# Thermal_MGMT.net
KiCad netlist of a schematic drawn in Altium Designer
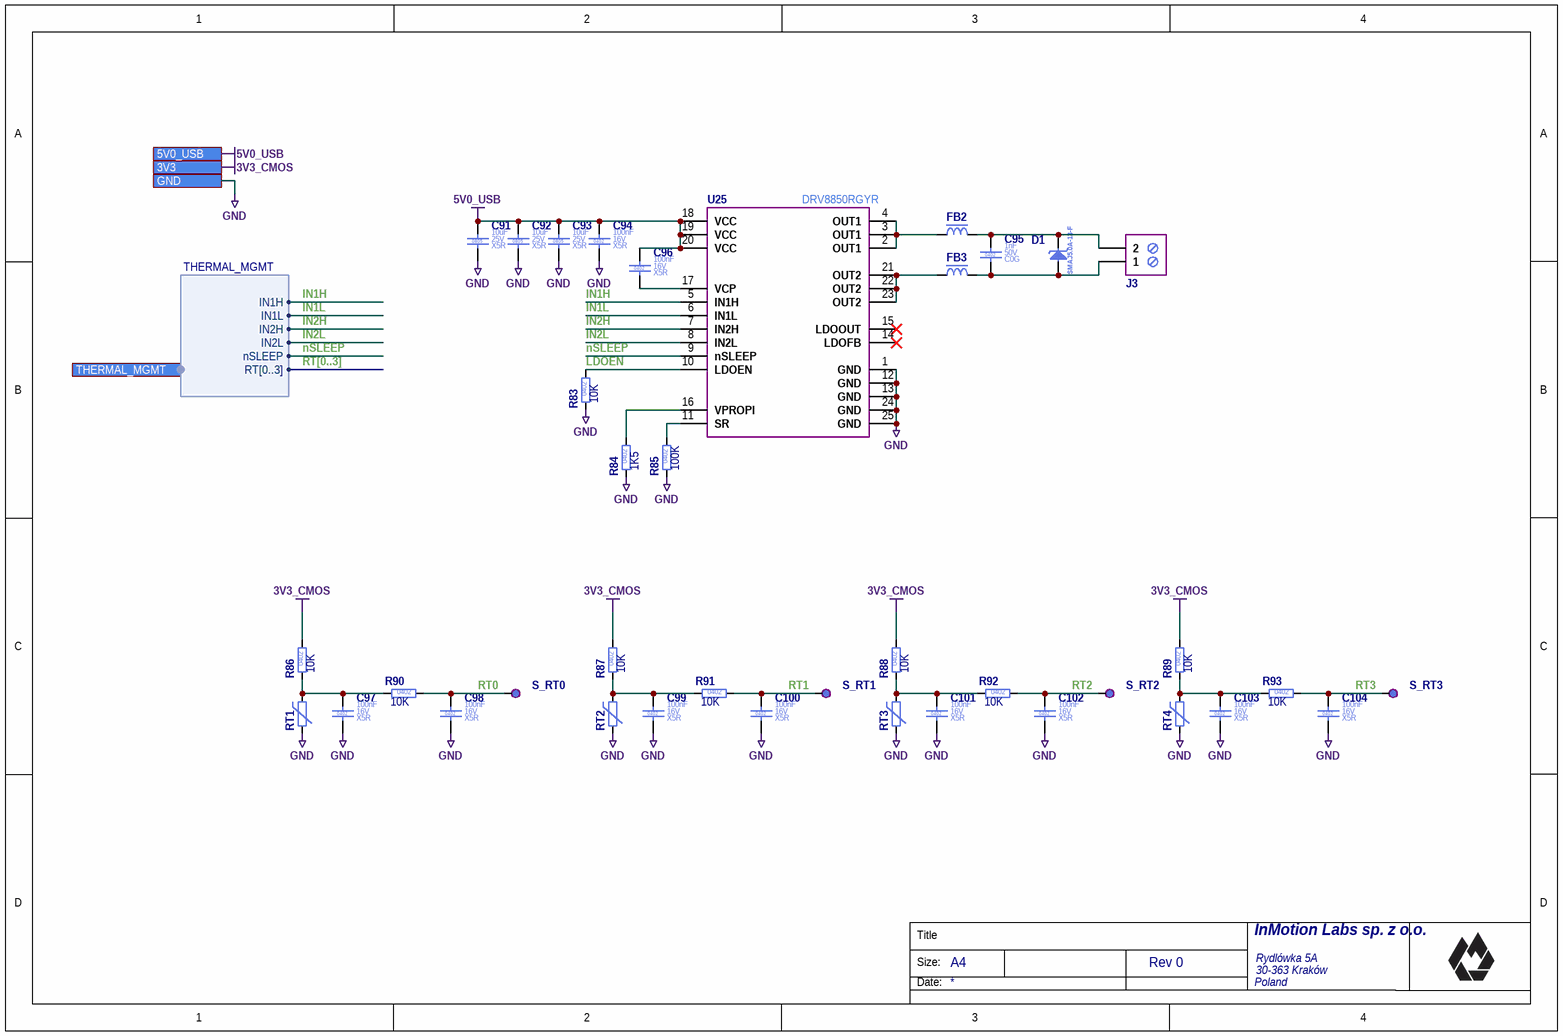
[diagram p0: Thermal_MGMT.SchDoc]

(export (version "E")
  (design (tool "Eeschema 10.0.6"))
  (components
    (comp (ref "C91")
      (value "C_10UF_25V_X5R_0805_10")
      (footprint "C_0805_2012")
      (description "Ceramic Capacitor")
      (fields
        (field (name "CASE/PACKAGE") "0805")
        (field (name "VOLTAGE RATING (DC)") "25V")
        (field (name "DIELECTRIC") "X5R")
        (field (name "CAPACITANCE") "10uF")
        (field (name "TOLERANCE") "10%")
        (field (name "MANUFACTURER PART NUMBER") "CL21A106KAYNNNE")
      )
      (libsource (lib "7Sigma") (part "C"))
    )
    (comp (ref "C92")
      (value "C_10UF_25V_X5R_0805_10")
      (footprint "C_0805_2012")
      (description "Ceramic Capacitor")
      (fields
        (field (name "CASE/PACKAGE") "0805")
        (field (name "VOLTAGE RATING (DC)") "25V")
        (field (name "DIELECTRIC") "X5R")
        (field (name "CAPACITANCE") "10uF")
        (field (name "TOLERANCE") "10%")
        (field (name "MANUFACTURER PART NUMBER") "CL21A106KAYNNNE")
      )
      (libsource (lib "7Sigma") (part "C"))
    )
    (comp (ref "C93")
      (value "C_10UF_25V_X5R_0805_10")
      (footprint "C_0805_2012")
      (description "Ceramic Capacitor")
      (fields
        (field (name "CASE/PACKAGE") "0805")
        (field (name "VOLTAGE RATING (DC)") "25V")
        (field (name "DIELECTRIC") "X5R")
        (field (name "CAPACITANCE") "10uF")
        (field (name "TOLERANCE") "10%")
        (field (name "MANUFACTURER PART NUMBER") "CL21A106KAYNNNE")
      )
      (libsource (lib "7Sigma") (part "C"))
    )
    (comp (ref "C94")
      (value "C_100NF_16V_X5R_0402_10")
      (footprint "C_0402_1005")
      (description "Ceramic Capacitor")
      (fields
        (field (name "CASE/PACKAGE") "0402")
        (field (name "VOLTAGE RATING (DC)") "16V")
        (field (name "DIELECTRIC") "X5R")
        (field (name "CAPACITANCE") "100nF")
        (field (name "TOLERANCE") "10%")
        (field (name "MANUFACTURER PART NUMBER") "EMK105BJ104KV-F")
      )
      (libsource (lib "7Sigma") (part "C"))
    )
    (comp (ref "C95")
      (value "C_1NF_50V_C0G_0402_5")
      (footprint "C_0402_1005")
      (description "Ceramic Capacitor")
      (fields
        (field (name "CASE/PACKAGE") "0402")
        (field (name "VOLTAGE RATING (DC)") "50V")
        (field (name "DIELECTRIC") "C0G")
        (field (name "CAPACITANCE") "1nF")
        (field (name "TOLERANCE") "5%")
        (field (name "MANUFACTURER PART NUMBER") "UMK105CG102JV-F")
      )
      (libsource (lib "7Sigma") (part "C"))
    )
    (comp (ref "C96")
      (value "C_100NF_16V_X5R_0402_10")
      (footprint "C_0402_1005")
      (description "Ceramic Capacitor")
      (fields
        (field (name "CASE/PACKAGE") "0402")
        (field (name "VOLTAGE RATING (DC)") "16V")
        (field (name "DIELECTRIC") "X5R")
        (field (name "CAPACITANCE") "100nF")
        (field (name "TOLERANCE") "10%")
        (field (name "MANUFACTURER PART NUMBER") "EMK105BJ104KV-F")
      )
      (libsource (lib "7Sigma") (part "C"))
    )
    (comp (ref "C97")
      (value "C_100NF_16V_X5R_0402_10")
      (footprint "C_0402_1005")
      (description "Ceramic Capacitor")
      (fields
        (field (name "CASE/PACKAGE") "0402")
        (field (name "VOLTAGE RATING (DC)") "16V")
        (field (name "DIELECTRIC") "X5R")
        (field (name "CAPACITANCE") "100nF")
        (field (name "TOLERANCE") "10%")
        (field (name "MANUFACTURER PART NUMBER") "EMK105BJ104KV-F")
      )
      (libsource (lib "7Sigma") (part "C"))
    )
    (comp (ref "C98")
      (value "C_100NF_16V_X5R_0402_10")
      (footprint "C_0402_1005")
      (description "Ceramic Capacitor")
      (fields
        (field (name "CASE/PACKAGE") "0402")
        (field (name "VOLTAGE RATING (DC)") "16V")
        (field (name "DIELECTRIC") "X5R")
        (field (name "CAPACITANCE") "100nF")
        (field (name "TOLERANCE") "10%")
        (field (name "MANUFACTURER PART NUMBER") "EMK105BJ104KV-F")
      )
      (libsource (lib "7Sigma") (part "C"))
    )
    (comp (ref "C99")
      (value "C_100NF_16V_X5R_0402_10")
      (footprint "C_0402_1005")
      (description "Ceramic Capacitor")
      (fields
        (field (name "CASE/PACKAGE") "0402")
        (field (name "VOLTAGE RATING (DC)") "16V")
        (field (name "DIELECTRIC") "X5R")
        (field (name "CAPACITANCE") "100nF")
        (field (name "TOLERANCE") "10%")
        (field (name "MANUFACTURER PART NUMBER") "EMK105BJ104KV-F")
      )
      (libsource (lib "7Sigma") (part "C"))
    )
    (comp (ref "C100")
      (value "C_100NF_16V_X5R_0402_10")
      (footprint "C_0402_1005")
      (description "Ceramic Capacitor")
      (fields
        (field (name "CASE/PACKAGE") "0402")
        (field (name "VOLTAGE RATING (DC)") "16V")
        (field (name "DIELECTRIC") "X5R")
        (field (name "CAPACITANCE") "100nF")
        (field (name "TOLERANCE") "10%")
        (field (name "MANUFACTURER PART NUMBER") "EMK105BJ104KV-F")
      )
      (libsource (lib "7Sigma") (part "C"))
    )
    (comp (ref "C101")
      (value "C_100NF_16V_X5R_0402_10")
      (footprint "C_0402_1005")
      (description "Ceramic Capacitor")
      (fields
        (field (name "CASE/PACKAGE") "0402")
        (field (name "VOLTAGE RATING (DC)") "16V")
        (field (name "DIELECTRIC") "X5R")
        (field (name "CAPACITANCE") "100nF")
        (field (name "TOLERANCE") "10%")
        (field (name "MANUFACTURER PART NUMBER") "EMK105BJ104KV-F")
      )
      (libsource (lib "7Sigma") (part "C"))
    )
    (comp (ref "C102")
      (value "C_100NF_16V_X5R_0402_10")
      (footprint "C_0402_1005")
      (description "Ceramic Capacitor")
      (fields
        (field (name "CASE/PACKAGE") "0402")
        (field (name "VOLTAGE RATING (DC)") "16V")
        (field (name "DIELECTRIC") "X5R")
        (field (name "CAPACITANCE") "100nF")
        (field (name "TOLERANCE") "10%")
        (field (name "MANUFACTURER PART NUMBER") "EMK105BJ104KV-F")
      )
      (libsource (lib "7Sigma") (part "C"))
    )
    (comp (ref "C103")
      (value "C_100NF_16V_X5R_0402_10")
      (footprint "C_0402_1005")
      (description "Ceramic Capacitor")
      (fields
        (field (name "CASE/PACKAGE") "0402")
        (field (name "VOLTAGE RATING (DC)") "16V")
        (field (name "DIELECTRIC") "X5R")
        (field (name "CAPACITANCE") "100nF")
        (field (name "TOLERANCE") "10%")
        (field (name "MANUFACTURER PART NUMBER") "EMK105BJ104KV-F")
      )
      (libsource (lib "7Sigma") (part "C"))
    )
    (comp (ref "C104")
      (value "C_100NF_16V_X5R_0402_10")
      (footprint "C_0402_1005")
      (description "Ceramic Capacitor")
      (fields
        (field (name "CASE/PACKAGE") "0402")
        (field (name "VOLTAGE RATING (DC)") "16V")
        (field (name "DIELECTRIC") "X5R")
        (field (name "CAPACITANCE") "100nF")
        (field (name "TOLERANCE") "10%")
        (field (name "MANUFACTURER PART NUMBER") "EMK105BJ104KV-F")
      )
      (libsource (lib "7Sigma") (part "C"))
    )
    (comp (ref "D1")
      (value "SMAJ5.0A-13-F")
      (footprint "DO-214AC")
      (description "ESD Suppressors / TVS Diodes")
      (fields (field (name "PART NUMBER") "SMAJ5.0A-13-F") (field (name "MANUFACTURER") "Diodes Inc"))
      (libsource (lib "7Sigma") (part "TVS_UNI"))
    )
    (comp (ref "FB2")
      (value "FBMJ1608HS220NTR")
      (footprint "FB_0603_1608")
      (description "Ferrite Bead")
      (fields (field (name "MANUFACTURER") "Taiyo Yuden") (field (name "TOLERANCE") "30"))
      (libsource (lib "7Sigma") (part "FB"))
    )
    (comp (ref "FB3")
      (value "FBMJ1608HS220NTR")
      (footprint "FB_0603_1608")
      (description "Ferrite Bead")
      (fields (field (name "MANUFACTURER") "Taiyo Yuden") (field (name "TOLERANCE") "30"))
      (libsource (lib "7Sigma") (part "FB"))
    )
    (comp (ref "J3")
      (value "691101710002")
      (footprint "691101710002")
      (description "PCB Terminal Block 1x2")
      (fields (field (name "MANUFACTURER") "Wurth Elektronik"))
      (libsource (lib "7Sigma") (part "ARK2"))
    )
    (comp (ref "R83")
      (value "R_10K_0402_1")
      (footprint "R_0402_1005")
      (description "Thick Film Resistor")
      (fields
        (field (name "RESISTANCE") "10K")
        (field (name "CASE/PACKAGE") "0402")
        (field (name "TOLERANCE") "1%")
        (field (name "MANUFACTURER") "Yageo")
      )
      (libsource (lib "7Sigma") (part "R"))
    )
    (comp (ref "R84")
      (value "R_1K5_0402_1")
      (footprint "R_0402_1005")
      (description "Thick Film Resistor")
      (fields
        (field (name "RESISTANCE") "1K5")
        (field (name "CASE/PACKAGE") "0402")
        (field (name "TOLERANCE") "1%")
        (field (name "MANUFACTURER") "Yageo")
      )
      (libsource (lib "7Sigma") (part "R"))
    )
    (comp (ref "R85")
      (value "R_100K_0402_1")
      (footprint "R_0402_1005")
      (description "Thick Film Resistor")
      (fields
        (field (name "RESISTANCE") "100K")
        (field (name "CASE/PACKAGE") "0402")
        (field (name "TOLERANCE") "1%")
        (field (name "MANUFACTURER") "Yageo")
      )
      (libsource (lib "7Sigma") (part "R"))
    )
    (comp (ref "R86")
      (value "R_10K_0402_1")
      (footprint "R_0402_1005")
      (description "Thick Film Resistor")
      (fields
        (field (name "RESISTANCE") "10K")
        (field (name "CASE/PACKAGE") "0402")
        (field (name "TOLERANCE") "1%")
        (field (name "MANUFACTURER") "Yageo")
      )
      (libsource (lib "7Sigma") (part "R"))
    )
    (comp (ref "R87")
      (value "R_10K_0402_1")
      (footprint "R_0402_1005")
      (description "Thick Film Resistor")
      (fields
        (field (name "RESISTANCE") "10K")
        (field (name "CASE/PACKAGE") "0402")
        (field (name "TOLERANCE") "1%")
        (field (name "MANUFACTURER") "Yageo")
      )
      (libsource (lib "7Sigma") (part "R"))
    )
    (comp (ref "R88")
      (value "R_10K_0402_1")
      (footprint "R_0402_1005")
      (description "Thick Film Resistor")
      (fields
        (field (name "RESISTANCE") "10K")
        (field (name "CASE/PACKAGE") "0402")
        (field (name "TOLERANCE") "1%")
        (field (name "MANUFACTURER") "Yageo")
      )
      (libsource (lib "7Sigma") (part "R"))
    )
    (comp (ref "R89")
      (value "R_10K_0402_1")
      (footprint "R_0402_1005")
      (description "Thick Film Resistor")
      (fields
        (field (name "RESISTANCE") "10K")
        (field (name "CASE/PACKAGE") "0402")
        (field (name "TOLERANCE") "1%")
        (field (name "MANUFACTURER") "Yageo")
      )
      (libsource (lib "7Sigma") (part "R"))
    )
    (comp (ref "R90")
      (value "R_10K_0402_1")
      (footprint "R_0402_1005")
      (description "Thick Film Resistor")
      (fields
        (field (name "RESISTANCE") "10K")
        (field (name "CASE/PACKAGE") "0402")
        (field (name "TOLERANCE") "1%")
        (field (name "MANUFACTURER") "Yageo")
      )
      (libsource (lib "7Sigma") (part "R"))
    )
    (comp (ref "R91")
      (value "R_10K_0402_1")
      (footprint "R_0402_1005")
      (description "Thick Film Resistor")
      (fields
        (field (name "RESISTANCE") "10K")
        (field (name "CASE/PACKAGE") "0402")
        (field (name "TOLERANCE") "1%")
        (field (name "MANUFACTURER") "Yageo")
      )
      (libsource (lib "7Sigma") (part "R"))
    )
    (comp (ref "R92")
      (value "R_10K_0402_1")
      (footprint "R_0402_1005")
      (description "Thick Film Resistor")
      (fields
        (field (name "RESISTANCE") "10K")
        (field (name "CASE/PACKAGE") "0402")
        (field (name "TOLERANCE") "1%")
        (field (name "MANUFACTURER") "Yageo")
      )
      (libsource (lib "7Sigma") (part "R"))
    )
    (comp (ref "R93")
      (value "R_10K_0402_1")
      (footprint "R_0402_1005")
      (description "Thick Film Resistor")
      (fields
        (field (name "RESISTANCE") "10K")
        (field (name "CASE/PACKAGE") "0402")
        (field (name "TOLERANCE") "1%")
        (field (name "MANUFACTURER") "Yageo")
      )
      (libsource (lib "7Sigma") (part "R"))
    )
    (comp (ref "RT1")
      (value "NCP15XH103J03RC")
      (footprint "R_0402_1005")
      (description "NTC Thermistor")
      (fields (field (name "MANUFACTURER") "Murata"))
      (libsource (lib "7Sigma") (part "RT"))
    )
    (comp (ref "RT2")
      (value "NCP15XH103J03RC")
      (footprint "R_0402_1005")
      (description "NTC Thermistor")
      (fields (field (name "MANUFACTURER") "Murata"))
      (libsource (lib "7Sigma") (part "RT"))
    )
    (comp (ref "RT3")
      (value "NCP15XH103J03RC")
      (footprint "R_0402_1005")
      (description "NTC Thermistor")
      (fields (field (name "MANUFACTURER") "Murata"))
      (libsource (lib "7Sigma") (part "RT"))
    )
    (comp (ref "RT4")
      (value "NCP15XH103J03RC")
      (footprint "R_0402_1005")
      (description "NTC Thermistor")
      (fields (field (name "MANUFACTURER") "Murata"))
      (libsource (lib "7Sigma") (part "RT"))
    )
    (comp (ref "S_RT0")
      (value "TP_PAD_1.3MM")
      (footprint "TP_PAD_1.3MM")
      (description "Testpoint SMD 1.3mm")
      (libsource (lib "7Sigma") (part "TESTPOINT"))
    )
    (comp (ref "S_RT1")
      (value "TP_PAD_1.3MM")
      (footprint "TP_PAD_1.3MM")
      (description "Testpoint SMD 1.3mm")
      (libsource (lib "7Sigma") (part "TESTPOINT"))
    )
    (comp (ref "S_RT2")
      (value "TP_PAD_1.3MM")
      (footprint "TP_PAD_1.3MM")
      (description "Testpoint SMD 1.3mm")
      (libsource (lib "7Sigma") (part "TESTPOINT"))
    )
    (comp (ref "S_RT3")
      (value "TP_PAD_1.3MM")
      (footprint "TP_PAD_1.3MM")
      (description "Testpoint SMD 1.3mm")
      (libsource (lib "7Sigma") (part "TESTPOINT"))
    )
    (comp (ref "U25")
      (value "DRV8850RGYR")
      (footprint "PQFN50P350X550X100_HS-25N")
      (description "Low Voltage H-Bridge IC With LDO Voltage Regulator")
      (fields
        (field (name "MANUFACTURER PART NUMBER") "DRV8850RGYR")
        (field (name "MANUFACTURER") "Texas Instruments")
      )
      (libsource (lib "7Sigma") (part "DRV8850"))
    )
  )
  (nets
    (net (code "2") (name "/IN1H") (class "Default")
      (node (ref "U25") (pin "5") (pinfunction "IN1H_5") (pintype "passive"))
    )
    (net (code "3") (name "/IN1L") (class "Default")
      (node (ref "U25") (pin "6") (pinfunction "IN1L_6") (pintype "passive"))
    )
    (net (code "4") (name "/IN2H") (class "Default")
      (node (ref "U25") (pin "7") (pinfunction "IN2H_7") (pintype "passive"))
    )
    (net (code "5") (name "/IN2L") (class "Default")
      (node (ref "U25") (pin "8") (pinfunction "IN2L_8") (pintype "passive"))
    )
    (net (code "6") (name "/LDOEN") (class "Default")
      (node (ref "R83") (pin "2") (pinfunction "2_2") (pintype "passive"))
      (node (ref "U25") (pin "10") (pinfunction "LDOEN_10") (pintype "passive"))
    )
    (net (code "7") (name "/RT0") (class "Default")
      (node (ref "C98") (pin "1") (pinfunction "1_1") (pintype "passive"))
      (node (ref "R90") (pin "2") (pinfunction "2_2") (pintype "passive"))
      (node (ref "S_RT0") (pin "1") (pinfunction "TP_1") (pintype "passive"))
    )
    (net (code "8") (name "/RT1") (class "Default")
      (node (ref "C100") (pin "1") (pinfunction "1_1") (pintype "passive"))
      (node (ref "R91") (pin "2") (pinfunction "2_2") (pintype "passive"))
      (node (ref "S_RT1") (pin "1") (pinfunction "TP_1") (pintype "passive"))
    )
    (net (code "9") (name "/RT2") (class "Default")
      (node (ref "C102") (pin "1") (pinfunction "1_1") (pintype "passive"))
      (node (ref "R92") (pin "2") (pinfunction "2_2") (pintype "passive"))
      (node (ref "S_RT2") (pin "1") (pinfunction "TP_1") (pintype "passive"))
    )
    (net (code "10") (name "/RT3") (class "Default")
      (node (ref "C104") (pin "1") (pinfunction "1_1") (pintype "passive"))
      (node (ref "R93") (pin "2") (pinfunction "2_2") (pintype "passive"))
      (node (ref "S_RT3") (pin "1") (pinfunction "TP_1") (pintype "passive"))
    )
    (net (code "12") (name "/nSLEEP") (class "Default")
      (node (ref "U25") (pin "9") (pinfunction "nSLEEP_9") (pintype "passive"))
    )
    (net (code "14") (name "3V3_CMOS") (class "Default")
      (node (ref "R86") (pin "2") (pinfunction "2_2") (pintype "passive"))
      (node (ref "R87") (pin "2") (pinfunction "2_2") (pintype "passive"))
      (node (ref "R88") (pin "2") (pinfunction "2_2") (pintype "passive"))
      (node (ref "R89") (pin "2") (pinfunction "2_2") (pintype "passive"))
    )
    (net (code "15") (name "5V0_USB") (class "Default")
      (node (ref "C91") (pin "1") (pinfunction "1_1") (pintype "passive"))
      (node (ref "C92") (pin "1") (pinfunction "1_1") (pintype "passive"))
      (node (ref "C93") (pin "1") (pinfunction "1_1") (pintype "passive"))
      (node (ref "C94") (pin "1") (pinfunction "1_1") (pintype "passive"))
      (node (ref "C96") (pin "1") (pinfunction "1_1") (pintype "passive"))
      (node (ref "U25") (pin "18") (pinfunction "VCC_18") (pintype "passive"))
      (node (ref "U25") (pin "19") (pinfunction "VCC_19") (pintype "passive"))
      (node (ref "U25") (pin "20") (pinfunction "VCC_20") (pintype "passive"))
    )
    (net (code "16") (name "GND") (class "Default")
      (node (ref "C100") (pin "2") (pinfunction "2_2") (pintype "passive"))
      (node (ref "C101") (pin "2") (pinfunction "2_2") (pintype "passive"))
      (node (ref "C102") (pin "2") (pinfunction "2_2") (pintype "passive"))
      (node (ref "C103") (pin "2") (pinfunction "2_2") (pintype "passive"))
      (node (ref "C104") (pin "2") (pinfunction "2_2") (pintype "passive"))
      (node (ref "C91") (pin "2") (pinfunction "2_2") (pintype "passive"))
      (node (ref "C92") (pin "2") (pinfunction "2_2") (pintype "passive"))
      (node (ref "C93") (pin "2") (pinfunction "2_2") (pintype "passive"))
      (node (ref "C94") (pin "2") (pinfunction "2_2") (pintype "passive"))
      (node (ref "C97") (pin "2") (pinfunction "2_2") (pintype "passive"))
      (node (ref "C98") (pin "2") (pinfunction "2_2") (pintype "passive"))
      (node (ref "C99") (pin "2") (pinfunction "2_2") (pintype "passive"))
      (node (ref "R83") (pin "1") (pinfunction "1_1") (pintype "passive"))
      (node (ref "R84") (pin "1") (pinfunction "1_1") (pintype "passive"))
      (node (ref "R85") (pin "1") (pinfunction "1_1") (pintype "passive"))
      (node (ref "RT1") (pin "1") (pinfunction "1_1") (pintype "passive"))
      (node (ref "RT2") (pin "1") (pinfunction "1_1") (pintype "passive"))
      (node (ref "RT3") (pin "1") (pinfunction "1_1") (pintype "passive"))
      (node (ref "RT4") (pin "1") (pinfunction "1_1") (pintype "passive"))
      (node (ref "U25") (pin "1") (pinfunction "GND_1") (pintype "passive"))
      (node (ref "U25") (pin "12") (pinfunction "GND_12") (pintype "passive"))
      (node (ref "U25") (pin "13") (pinfunction "GND_13") (pintype "passive"))
      (node (ref "U25") (pin "24") (pinfunction "GND_24") (pintype "passive"))
      (node (ref "U25") (pin "25") (pinfunction "GND_25") (pintype "passive"))
    )
    (net (code "17") (name "Net-(C97-Pad1)") (class "Default")
      (node (ref "C97") (pin "1") (pinfunction "1_1") (pintype "passive"))
      (node (ref "R86") (pin "1") (pinfunction "1_1") (pintype "passive"))
      (node (ref "R90") (pin "1") (pinfunction "1_1") (pintype "passive"))
      (node (ref "RT1") (pin "2") (pinfunction "2_2") (pintype "passive"))
    )
    (net (code "18") (name "Net-(C99-Pad1)") (class "Default")
      (node (ref "C99") (pin "1") (pinfunction "1_1") (pintype "passive"))
      (node (ref "R87") (pin "1") (pinfunction "1_1") (pintype "passive"))
      (node (ref "R91") (pin "1") (pinfunction "1_1") (pintype "passive"))
      (node (ref "RT2") (pin "2") (pinfunction "2_2") (pintype "passive"))
    )
    (net (code "19") (name "Net-(C101-Pad1)") (class "Default")
      (node (ref "C101") (pin "1") (pinfunction "1_1") (pintype "passive"))
      (node (ref "R88") (pin "1") (pinfunction "1_1") (pintype "passive"))
      (node (ref "R92") (pin "1") (pinfunction "1_1") (pintype "passive"))
      (node (ref "RT3") (pin "2") (pinfunction "2_2") (pintype "passive"))
    )
    (net (code "20") (name "Net-(C103-Pad1)") (class "Default")
      (node (ref "C103") (pin "1") (pinfunction "1_1") (pintype "passive"))
      (node (ref "R89") (pin "1") (pinfunction "1_1") (pintype "passive"))
      (node (ref "R93") (pin "1") (pinfunction "1_1") (pintype "passive"))
      (node (ref "RT4") (pin "2") (pinfunction "2_2") (pintype "passive"))
    )
    (net (code "21") (name "Net-(D1-A)") (class "Default")
      (node (ref "C95") (pin "2") (pinfunction "2_2") (pintype "passive"))
      (node (ref "D1") (pin "2") (pinfunction "A_2") (pintype "passive"))
      (node (ref "FB3") (pin "2") (pinfunction "2_2") (pintype "passive"))
      (node (ref "J3") (pin "1") (pinfunction "1_1") (pintype "passive"))
    )
    (net (code "22") (name "Net-(D1-C)") (class "Default")
      (node (ref "C95") (pin "1") (pinfunction "1_1") (pintype "passive"))
      (node (ref "D1") (pin "1") (pinfunction "C_1") (pintype "passive"))
      (node (ref "FB2") (pin "2") (pinfunction "2_2") (pintype "passive"))
      (node (ref "J3") (pin "2") (pinfunction "2_2") (pintype "passive"))
    )
    (net (code "23") (name "Net-(FB2-Pad1)") (class "Default")
      (node (ref "FB2") (pin "1") (pinfunction "1_1") (pintype "passive"))
      (node (ref "U25") (pin "2") (pinfunction "OUT1_2") (pintype "passive"))
      (node (ref "U25") (pin "3") (pinfunction "OUT1_3") (pintype "passive"))
      (node (ref "U25") (pin "4") (pinfunction "OUT1_4") (pintype "passive"))
    )
    (net (code "24") (name "Net-(FB3-Pad1)") (class "Default")
      (node (ref "FB3") (pin "1") (pinfunction "1_1") (pintype "passive"))
      (node (ref "U25") (pin "21") (pinfunction "OUT2_21") (pintype "passive"))
      (node (ref "U25") (pin "22") (pinfunction "OUT2_22") (pintype "passive"))
      (node (ref "U25") (pin "23") (pinfunction "OUT2_23") (pintype "passive"))
    )
    (net (code "25") (name "Net-(U25-SR)") (class "Default")
      (node (ref "R85") (pin "2") (pinfunction "2_2") (pintype "passive"))
      (node (ref "U25") (pin "11") (pinfunction "SR_11") (pintype "passive"))
    )
    (net (code "26") (name "Net-(U25-VCP)") (class "Default")
      (node (ref "C96") (pin "2") (pinfunction "2_2") (pintype "passive"))
      (node (ref "U25") (pin "17") (pinfunction "VCP_17") (pintype "passive"))
    )
    (net (code "27") (name "Net-(U25-VPROPI)") (class "Default")
      (node (ref "R84") (pin "2") (pinfunction "2_2") (pintype "passive"))
      (node (ref "U25") (pin "16") (pinfunction "VPROPI_16") (pintype "passive"))
    )
    (net (code "28") (name "unconnected-(U25-LDOFB-Pad14)") (class "Default")
      (node (ref "U25") (pin "14") (pinfunction "LDOFB_14") (pintype "passive+no_connect"))
    )
    (net (code "29") (name "unconnected-(U25-LDOOUT-Pad15)") (class "Default")
      (node (ref "U25") (pin "15") (pinfunction "LDOOUT_15") (pintype "passive+no_connect"))
    )
  )
)
